# MCU_B.net
KiCad netlist of a schematic drawn in Altium Designer
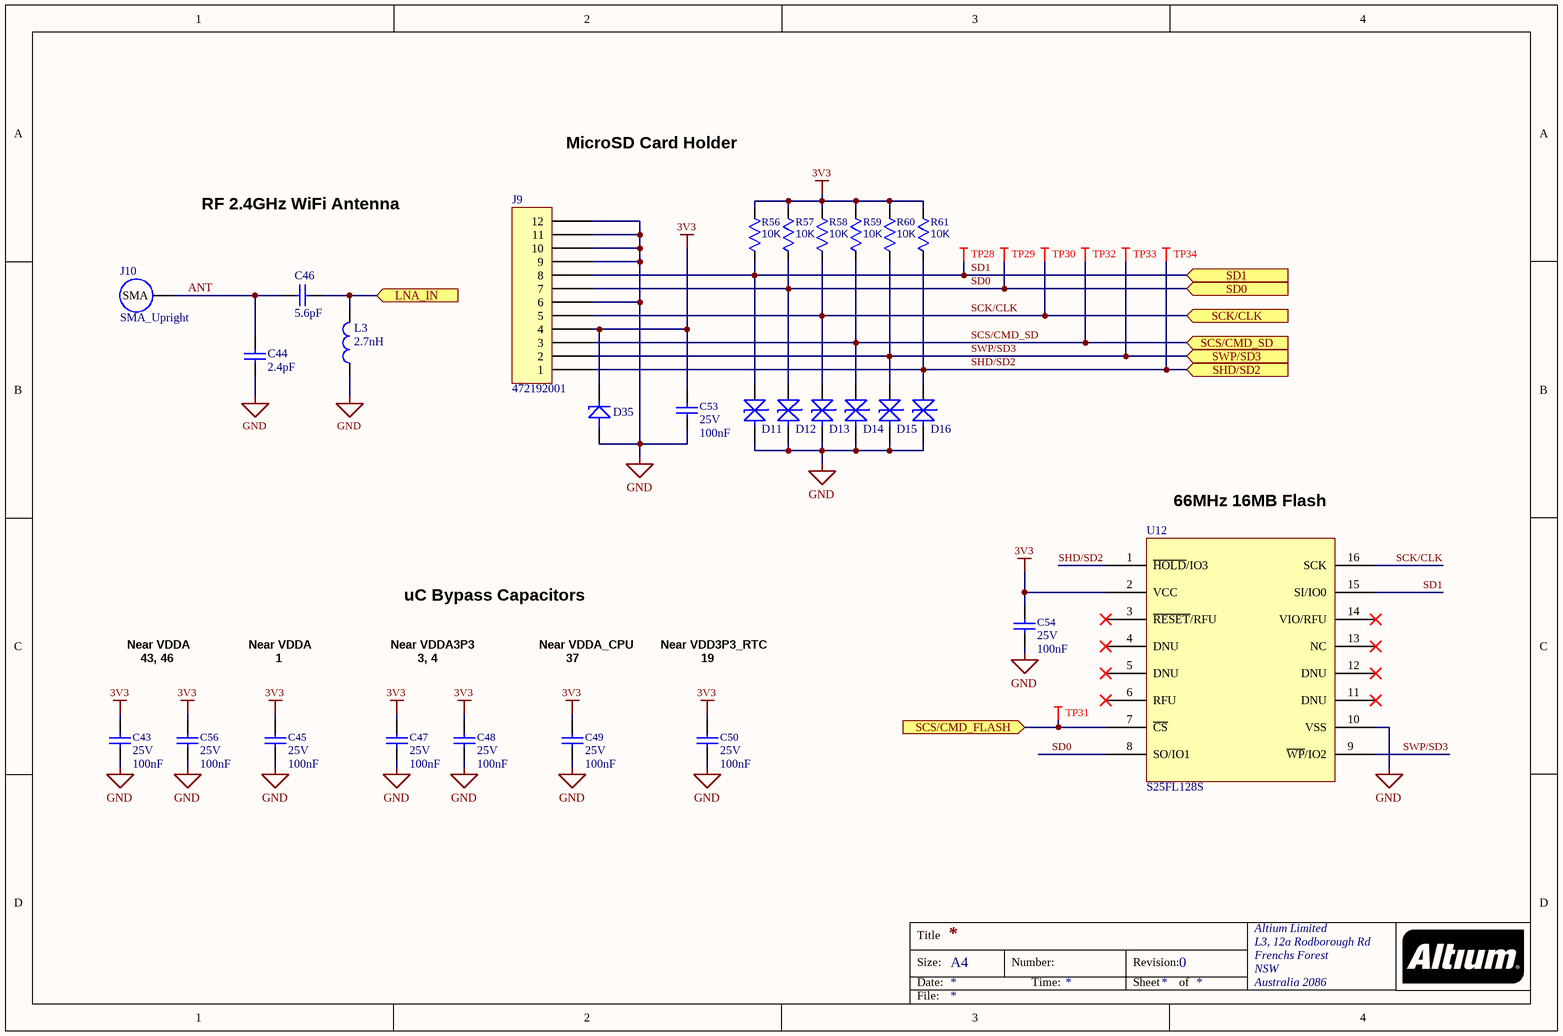
[diagram p0: MCU B.SchDoc]

(export (version "E")
  (design (tool "Eeschema 10.0.6"))
  (components
    (comp (ref "C43")
      (value "100nF")
      (footprint "CAPC1005X06N")
      (fields
        (field (name "VOLTAGE") "25V")
        (field (name "MANUFACTURER PART NUMBER") "CL05A104KA5NNNC")
        (field (name "MANUFACTURER") "Samsung")
        (field (name "Comment") "4.7uF")
      )
      (libsource (lib "Capacitors") (part "4.7uF_0603_10V"))
    )
    (comp (ref "C44")
      (value "2.4pF")
      (footprint "C1608[0603]")
      (description "Cap,2.4pF,100V,C0G/NP0,RF,0603")
      (fields
        (field (name "MANUFACTURER PART NUMBER") "GQM1885C2A2R4BB01D")
        (field (name "MANUFACTURER") "Murata Electronics North America")
      )
      (libsource (lib "Capacitors") (part "2.4pF_0603_100V"))
    )
    (comp (ref "C45")
      (value "100nF")
      (footprint "CAPC1005X06N")
      (fields
        (field (name "VOLTAGE") "25V")
        (field (name "MANUFACTURER PART NUMBER") "CL05A104KA5NNNC")
        (field (name "MANUFACTURER") "Samsung")
        (field (name "Comment") "4.7uF")
      )
      (libsource (lib "Capacitors") (part "4.7uF_0603_10V"))
    )
    (comp (ref "C46")
      (value "5.6pF")
      (footprint "C1608[0603]")
      (description "Cap,5.6pF,200V,C0G/NP0,RF,0603")
      (fields
        (field (name "MANUFACTURER PART NUMBER") "C0603C569C5GACTU")
        (field (name "MANUFACTURER") "KEMET")
      )
      (libsource (lib "Capacitors") (part "5.6pF_0603_200V"))
    )
    (comp (ref "C47")
      (value "100nF")
      (footprint "CAPC1005X06N")
      (fields
        (field (name "VOLTAGE") "25V")
        (field (name "MANUFACTURER PART NUMBER") "CL05A104KA5NNNC")
        (field (name "MANUFACTURER") "Samsung")
        (field (name "Comment") "4.7uF")
      )
      (libsource (lib "Capacitors") (part "4.7uF_0603_10V"))
    )
    (comp (ref "C48")
      (value "100nF")
      (footprint "CAPC1005X06N")
      (fields
        (field (name "VOLTAGE") "25V")
        (field (name "MANUFACTURER PART NUMBER") "CL05A104KA5NNNC")
        (field (name "MANUFACTURER") "Samsung")
        (field (name "Comment") "4.7uF")
      )
      (libsource (lib "Capacitors") (part "4.7uF_0603_10V"))
    )
    (comp (ref "C49")
      (value "100nF")
      (footprint "CAPC1005X06N")
      (fields
        (field (name "VOLTAGE") "25V")
        (field (name "MANUFACTURER PART NUMBER") "CL05A104KA5NNNC")
        (field (name "MANUFACTURER") "Samsung")
        (field (name "Comment") "4.7uF")
      )
      (libsource (lib "Capacitors") (part "4.7uF_0603_10V"))
    )
    (comp (ref "C50")
      (value "100nF")
      (footprint "CAPC1005X06N")
      (fields
        (field (name "VOLTAGE") "25V")
        (field (name "MANUFACTURER PART NUMBER") "CL05A104KA5NNNC")
        (field (name "MANUFACTURER") "Samsung")
        (field (name "Comment") "4.7uF")
      )
      (libsource (lib "Capacitors") (part "4.7uF_0603_10V"))
    )
    (comp (ref "C53")
      (value "100nF")
      (footprint "CAPC1005X06N")
      (fields
        (field (name "VOLTAGE") "25V")
        (field (name "MANUFACTURER PART NUMBER") "CL05A104KA5NNNC")
        (field (name "MANUFACTURER") "Samsung")
        (field (name "Comment") "4.7uF")
      )
      (libsource (lib "Capacitors") (part "4.7uF_0603_10V"))
    )
    (comp (ref "C54")
      (value "100nF")
      (footprint "CAPC1005X06N")
      (fields
        (field (name "VOLTAGE") "25V")
        (field (name "MANUFACTURER PART NUMBER") "CL05A104KA5NNNC")
        (field (name "MANUFACTURER") "Samsung")
        (field (name "Comment") "4.7uF")
      )
      (libsource (lib "Capacitors") (part "4.7uF_0603_10V"))
    )
    (comp (ref "C56")
      (value "100nF")
      (footprint "CAPC1005X06N")
      (fields
        (field (name "VOLTAGE") "25V")
        (field (name "MANUFACTURER PART NUMBER") "CL05A104KA5NNNC")
        (field (name "MANUFACTURER") "Samsung")
        (field (name "Comment") "4.7uF")
      )
      (libsource (lib "Capacitors") (part "4.7uF_0603_10V"))
    )
    (comp (ref "D11")
      (value "ESD7951ST5GOSCT-ND")
      (footprint "SODFL100X40-2N")
      (description "TVS Diode")
      (fields
        (field (name "MANUFACTURER PART NUMBER") "ESD7951ST5G")
        (field (name "MANUFACTURER") "ON Semiconductor")
      )
      (libsource (lib "Gas Monitor Components") (part "ESD7951S"))
    )
    (comp (ref "D12")
      (value "ESD7951ST5GOSCT-ND")
      (footprint "SODFL100X40-2N")
      (description "TVS Diode")
      (fields
        (field (name "MANUFACTURER PART NUMBER") "ESD7951ST5G")
        (field (name "MANUFACTURER") "ON Semiconductor")
      )
      (libsource (lib "Gas Monitor Components") (part "ESD7951S"))
    )
    (comp (ref "D13")
      (value "ESD7951ST5GOSCT-ND")
      (footprint "SODFL100X40-2N")
      (description "TVS Diode")
      (fields
        (field (name "MANUFACTURER PART NUMBER") "ESD7951ST5G")
        (field (name "MANUFACTURER") "ON Semiconductor")
      )
      (libsource (lib "Gas Monitor Components") (part "ESD7951S"))
    )
    (comp (ref "D14")
      (value "ESD7951ST5GOSCT-ND")
      (footprint "SODFL100X40-2N")
      (description "TVS Diode")
      (fields
        (field (name "MANUFACTURER PART NUMBER") "ESD7951ST5G")
        (field (name "MANUFACTURER") "ON Semiconductor")
      )
      (libsource (lib "Gas Monitor Components") (part "ESD7951S"))
    )
    (comp (ref "D15")
      (value "ESD7951ST5GOSCT-ND")
      (footprint "SODFL100X40-2N")
      (description "TVS Diode")
      (fields
        (field (name "MANUFACTURER PART NUMBER") "ESD7951ST5G")
        (field (name "MANUFACTURER") "ON Semiconductor")
      )
      (libsource (lib "Gas Monitor Components") (part "ESD7951S"))
    )
    (comp (ref "D16")
      (value "ESD7951ST5GOSCT-ND")
      (footprint "SODFL100X40-2N")
      (description "TVS Diode")
      (fields
        (field (name "MANUFACTURER PART NUMBER") "ESD7951ST5G")
        (field (name "MANUFACTURER") "ON Semiconductor")
      )
      (libsource (lib "Gas Monitor Components") (part "ESD7951S"))
    )
    (comp (ref "D35")
      (value "3.3V TVS")
      (footprint "NXP PTVSxS1UR-Series (SOD123W)")
      (fields
        (field (name "MANUFACTURER") "Nexperia")
        (field (name "MANUFACTURER PART NUMBER") "PTVS3V3S1UTR,115")
      )
      (libsource (lib "FSM_2018") (part "NXP PTVSxS1UR-Series"))
    )
    (comp (ref "J9")
      (value "472192001")
      (footprint "SD-47219-001")
      (fields (field (name "MANUFACTURER") "Molex") (field (name "MANUFACTURER PART NUMBER") "0472192001"))
      (libsource (lib "Gas Monitor Components") (part "CON12"))
    )
    (comp (ref "J10")
      (value "SMA_Upright")
      (footprint "TE_5-1814400-1 Upright")
      (fields (field (name "MANUFACTURER") "Molex") (field (name "MANUFACTURER PART NUMBER") "0733910070"))
      (libsource (lib "Connectors") (part "SMA_Upright"))
    )
    (comp (ref "L3")
      (value "2.7nH")
      (footprint "L1608[0603]")
      (description "Ind,2.7nH,300mA,100mOhm DCR,13@100MHz,0603")
      (fields
        (field (name "MANUFACTURER PART NUMBER") "L0603C2N7SRMST")
        (field (name "MANUFACTURER") "KEMET")
      )
      (libsource (lib "Inductors") (part "2.7nH_0603"))
    )
    (comp (ref "R56")
      (value "10K")
      (footprint "RESC1005X03N")
      (description "RES 1K Ohm ±5%, 0.25W,1/4W 0603")
      (fields
        (field (name "MANUFACTURER") "Panasonic")
        (field (name "MANUFACTURER PART NUMBER") "ERJ-2RKF1002X")
      )
      (libsource (lib "Resistors") (part "1K00_0603_0.1W"))
    )
    (comp (ref "R57")
      (value "10K")
      (footprint "RESC1005X03N")
      (description "RES 1K Ohm ±5%, 0.25W,1/4W 0603")
      (fields
        (field (name "MANUFACTURER") "Panasonic")
        (field (name "MANUFACTURER PART NUMBER") "ERJ-2RKF1002X")
      )
      (libsource (lib "Resistors") (part "1K00_0603_0.1W"))
    )
    (comp (ref "R58")
      (value "10K")
      (footprint "RESC1005X03N")
      (description "RES 1K Ohm ±5%, 0.25W,1/4W 0603")
      (fields
        (field (name "MANUFACTURER") "Panasonic")
        (field (name "MANUFACTURER PART NUMBER") "ERJ-2RKF1002X")
      )
      (libsource (lib "Resistors") (part "1K00_0603_0.1W"))
    )
    (comp (ref "R59")
      (value "10K")
      (footprint "RESC1005X03N")
      (description "RES 1K Ohm ±5%, 0.25W,1/4W 0603")
      (fields
        (field (name "MANUFACTURER") "Panasonic")
        (field (name "MANUFACTURER PART NUMBER") "ERJ-2RKF1002X")
      )
      (libsource (lib "Resistors") (part "1K00_0603_0.1W"))
    )
    (comp (ref "R60")
      (value "10K")
      (footprint "RESC1005X03N")
      (description "RES 1K Ohm ±5%, 0.25W,1/4W 0603")
      (fields
        (field (name "MANUFACTURER") "Panasonic")
        (field (name "MANUFACTURER PART NUMBER") "ERJ-2RKF1002X")
      )
      (libsource (lib "Resistors") (part "1K00_0603_0.1W"))
    )
    (comp (ref "R61")
      (value "10K")
      (footprint "RESC1005X03N")
      (description "RES 1K Ohm ±5%, 0.25W,1/4W 0603")
      (fields
        (field (name "MANUFACTURER") "Panasonic")
        (field (name "MANUFACTURER PART NUMBER") "ERJ-2RKF1002X")
      )
      (libsource (lib "Resistors") (part "1K00_0603_0.1W"))
    )
    (comp (ref "TP28")
      (value "PAD")
      (footprint "TP_SMD_39MIL")
      (description "SMD Test Pad")
      (fields (field (name "MANUFACTURER") "No P/N Required"))
      (libsource (lib "Connectors") (part "TP_SMD_39MIL"))
    )
    (comp (ref "TP29")
      (value "PAD")
      (footprint "TP_SMD_39MIL")
      (description "SMD Test Pad")
      (fields (field (name "MANUFACTURER") "No P/N Required"))
      (libsource (lib "Connectors") (part "TP_SMD_39MIL"))
    )
    (comp (ref "TP30")
      (value "PAD")
      (footprint "TP_SMD_39MIL")
      (description "SMD Test Pad")
      (fields (field (name "MANUFACTURER") "No P/N Required"))
      (libsource (lib "Connectors") (part "TP_SMD_39MIL"))
    )
    (comp (ref "TP31")
      (value "PAD")
      (footprint "TP_SMD_39MIL")
      (description "SMD Test Pad")
      (fields (field (name "MANUFACTURER") "No P/N Required"))
      (libsource (lib "Connectors") (part "TP_SMD_39MIL"))
    )
    (comp (ref "TP32")
      (value "PAD")
      (footprint "TP_SMD_39MIL")
      (description "SMD Test Pad")
      (fields (field (name "MANUFACTURER") "No P/N Required"))
      (libsource (lib "Connectors") (part "TP_SMD_39MIL"))
    )
    (comp (ref "TP33")
      (value "PAD")
      (footprint "TP_SMD_39MIL")
      (description "SMD Test Pad")
      (fields (field (name "MANUFACTURER") "No P/N Required"))
      (libsource (lib "Connectors") (part "TP_SMD_39MIL"))
    )
    (comp (ref "TP34")
      (value "PAD")
      (footprint "TP_SMD_39MIL")
      (description "SMD Test Pad")
      (fields (field (name "MANUFACTURER") "No P/N Required"))
      (libsource (lib "Connectors") (part "TP_SMD_39MIL"))
    )
    (comp (ref "U12")
      (value "S25FL128S")
      (footprint "SOIC127P1030X265-16N")
      (description "QSPI 128M Flash Memory")
      (fields
        (field (name "MANUFACTURER") "Cypress Semiconductor Corp")
        (field (name "MANUFACTURER PART NUMBER") "S25FL128SDPMFIG10")
      )
      (libsource (lib "Gas Monitor Components") (part "S25FL128S"))
    )
  )
  (nets
    (net (code "1") (name "/ANT") (class "Default")
      (node (ref "C44") (pin "2") (pintype "passive"))
      (node (ref "C46") (pin "2") (pintype "passive"))
      (node (ref "J10") (pin "1") (pinfunction "SMA_1") (pintype "passive"))
    )
    (net (code "2") (name "/LNA_IN") (class "Default")
      (node (ref "C46") (pin "1") (pintype "passive"))
      (node (ref "L3") (pin "2") (pintype "passive"))
    )
    (net (code "3") (name "/SCK{slash}CLK") (class "Default")
      (node (ref "D13") (pin "2") (pinfunction "ANODE_2") (pintype "passive"))
      (node (ref "J9") (pin "5") (pinfunction "5_5") (pintype "passive"))
      (node (ref "R58") (pin "1") (pintype "passive"))
      (node (ref "TP30") (pin "1") (pintype "passive"))
      (node (ref "U12") (pin "16") (pinfunction "SCK_16") (pintype "passive"))
    )
    (net (code "4") (name "/SCS{slash}CMD_FLASH") (class "Default")
      (node (ref "TP31") (pin "1") (pintype "passive"))
      (node (ref "U12") (pin "7") (pinfunction "~{CS}_7") (pintype "passive"))
    )
    (net (code "5") (name "/SCS{slash}CMD_SD") (class "Default")
      (node (ref "D14") (pin "2") (pinfunction "ANODE_2") (pintype "passive"))
      (node (ref "J9") (pin "3") (pinfunction "3_3") (pintype "passive"))
      (node (ref "R59") (pin "1") (pintype "passive"))
      (node (ref "TP32") (pin "1") (pintype "passive"))
    )
    (net (code "6") (name "/SD0") (class "Default")
      (node (ref "D12") (pin "2") (pinfunction "ANODE_2") (pintype "passive"))
      (node (ref "J9") (pin "7") (pinfunction "7_7") (pintype "passive"))
      (node (ref "R57") (pin "1") (pintype "passive"))
      (node (ref "TP29") (pin "1") (pintype "passive"))
      (node (ref "U12") (pin "8") (pinfunction "SO/IO1_8") (pintype "passive"))
    )
    (net (code "7") (name "/SD1") (class "Default")
      (node (ref "D11") (pin "2") (pinfunction "ANODE_2") (pintype "passive"))
      (node (ref "J9") (pin "8") (pinfunction "8_8") (pintype "passive"))
      (node (ref "R56") (pin "1") (pintype "passive"))
      (node (ref "TP28") (pin "1") (pintype "passive"))
      (node (ref "U12") (pin "15") (pinfunction "SI/IO0_15") (pintype "passive"))
    )
    (net (code "8") (name "/SHD{slash}SD2") (class "Default")
      (node (ref "D16") (pin "2") (pinfunction "ANODE_2") (pintype "passive"))
      (node (ref "J9") (pin "1") (pinfunction "1_1") (pintype "passive"))
      (node (ref "R61") (pin "1") (pintype "passive"))
      (node (ref "TP34") (pin "1") (pintype "passive"))
      (node (ref "U12") (pin "1") (pinfunction "~{HOLD}/IO3_1") (pintype "passive"))
    )
    (net (code "9") (name "/SWP{slash}SD3") (class "Default")
      (node (ref "D15") (pin "2") (pinfunction "ANODE_2") (pintype "passive"))
      (node (ref "J9") (pin "2") (pinfunction "2_2") (pintype "passive"))
      (node (ref "R60") (pin "1") (pintype "passive"))
      (node (ref "TP33") (pin "1") (pintype "passive"))
      (node (ref "U12") (pin "9") (pinfunction "~{WP}/IO2_9") (pintype "passive"))
    )
    (net (code "10") (name "3V3") (class "Default")
      (node (ref "C43") (pin "1") (pintype "passive"))
      (node (ref "C45") (pin "1") (pintype "passive"))
      (node (ref "C47") (pin "1") (pintype "passive"))
      (node (ref "C48") (pin "1") (pintype "passive"))
      (node (ref "C49") (pin "1") (pintype "passive"))
      (node (ref "C50") (pin "1") (pintype "passive"))
      (node (ref "C53") (pin "1") (pintype "passive"))
      (node (ref "C54") (pin "1") (pintype "passive"))
      (node (ref "C56") (pin "1") (pintype "passive"))
      (node (ref "D35") (pin "1") (pinfunction "1_1") (pintype "passive"))
      (node (ref "J9") (pin "4") (pinfunction "4_4") (pintype "passive"))
      (node (ref "R56") (pin "2") (pintype "passive"))
      (node (ref "R57") (pin "2") (pintype "passive"))
      (node (ref "R58") (pin "2") (pintype "passive"))
      (node (ref "R59") (pin "2") (pintype "passive"))
      (node (ref "R60") (pin "2") (pintype "passive"))
      (node (ref "R61") (pin "2") (pintype "passive"))
      (node (ref "U12") (pin "2") (pinfunction "VCC_2") (pintype "power_in"))
    )
    (net (code "11") (name "GND") (class "Default")
      (node (ref "C43") (pin "2") (pintype "passive"))
      (node (ref "C44") (pin "1") (pintype "passive"))
      (node (ref "C45") (pin "2") (pintype "passive"))
      (node (ref "C47") (pin "2") (pintype "passive"))
      (node (ref "C48") (pin "2") (pintype "passive"))
      (node (ref "C49") (pin "2") (pintype "passive"))
      (node (ref "C50") (pin "2") (pintype "passive"))
      (node (ref "C53") (pin "2") (pintype "passive"))
      (node (ref "C54") (pin "2") (pintype "passive"))
      (node (ref "C56") (pin "2") (pintype "passive"))
      (node (ref "D11") (pin "1") (pinfunction "CATHODE_1") (pintype "passive"))
      (node (ref "D12") (pin "1") (pinfunction "CATHODE_1") (pintype "passive"))
      (node (ref "D13") (pin "1") (pinfunction "CATHODE_1") (pintype "passive"))
      (node (ref "D14") (pin "1") (pinfunction "CATHODE_1") (pintype "passive"))
      (node (ref "D15") (pin "1") (pinfunction "CATHODE_1") (pintype "passive"))
      (node (ref "D16") (pin "1") (pinfunction "CATHODE_1") (pintype "passive"))
      (node (ref "D35") (pin "2") (pinfunction "2_2") (pintype "passive"))
      (node (ref "J9") (pin "10") (pinfunction "10_10") (pintype "passive"))
      (node (ref "J9") (pin "11") (pinfunction "11_11") (pintype "passive"))
      (node (ref "J9") (pin "12") (pinfunction "12_12") (pintype "passive"))
      (node (ref "J9") (pin "6") (pinfunction "6_6") (pintype "passive"))
      (node (ref "J9") (pin "9") (pinfunction "9_9") (pintype "passive"))
      (node (ref "L3") (pin "1") (pintype "passive"))
      (node (ref "U12") (pin "10") (pinfunction "VSS_10") (pintype "power_in"))
    )
    (net (code "12") (name "unconnected-(U12-DNU-Pad4)") (class "Default")
      (node (ref "U12") (pin "4") (pinfunction "DNU_4") (pintype "passive+no_connect"))
    )
    (net (code "13") (name "unconnected-(U12-DNU-Pad5)") (class "Default")
      (node (ref "U12") (pin "5") (pinfunction "DNU_5") (pintype "passive+no_connect"))
    )
    (net (code "14") (name "unconnected-(U12-DNU-Pad11)") (class "Default")
      (node (ref "U12") (pin "11") (pinfunction "DNU_11") (pintype "passive+no_connect"))
    )
    (net (code "15") (name "unconnected-(U12-DNU-Pad12)") (class "Default")
      (node (ref "U12") (pin "12") (pinfunction "DNU_12") (pintype "passive+no_connect"))
    )
    (net (code "16") (name "unconnected-(U12-NC-Pad13)") (class "Default")
      (node (ref "U12") (pin "13") (pinfunction "NC_13") (pintype "passive+no_connect"))
    )
    (net (code "17") (name "unconnected-(U12-RFU-Pad6)") (class "Default")
      (node (ref "U12") (pin "6") (pinfunction "RFU_6") (pintype "passive+no_connect"))
    )
    (net (code "18") (name "unconnected-(U12-VIO{slash}RFU-Pad14)") (class "Default")
      (node (ref "U12") (pin "14") (pinfunction "VIO/RFU_14") (pintype "power_in+no_connect"))
    )
    (net (code "19") (name "unconnected-(U12-~{RESET}{slash}RFU-Pad3)") (class "Default")
      (node (ref "U12") (pin "3") (pinfunction "~{RESET}/RFU_3") (pintype "passive+no_connect"))
    )
  )
)
